# MOD-Z_01_V02.net
KiCad netlist of a schematic drawn in EAGLE
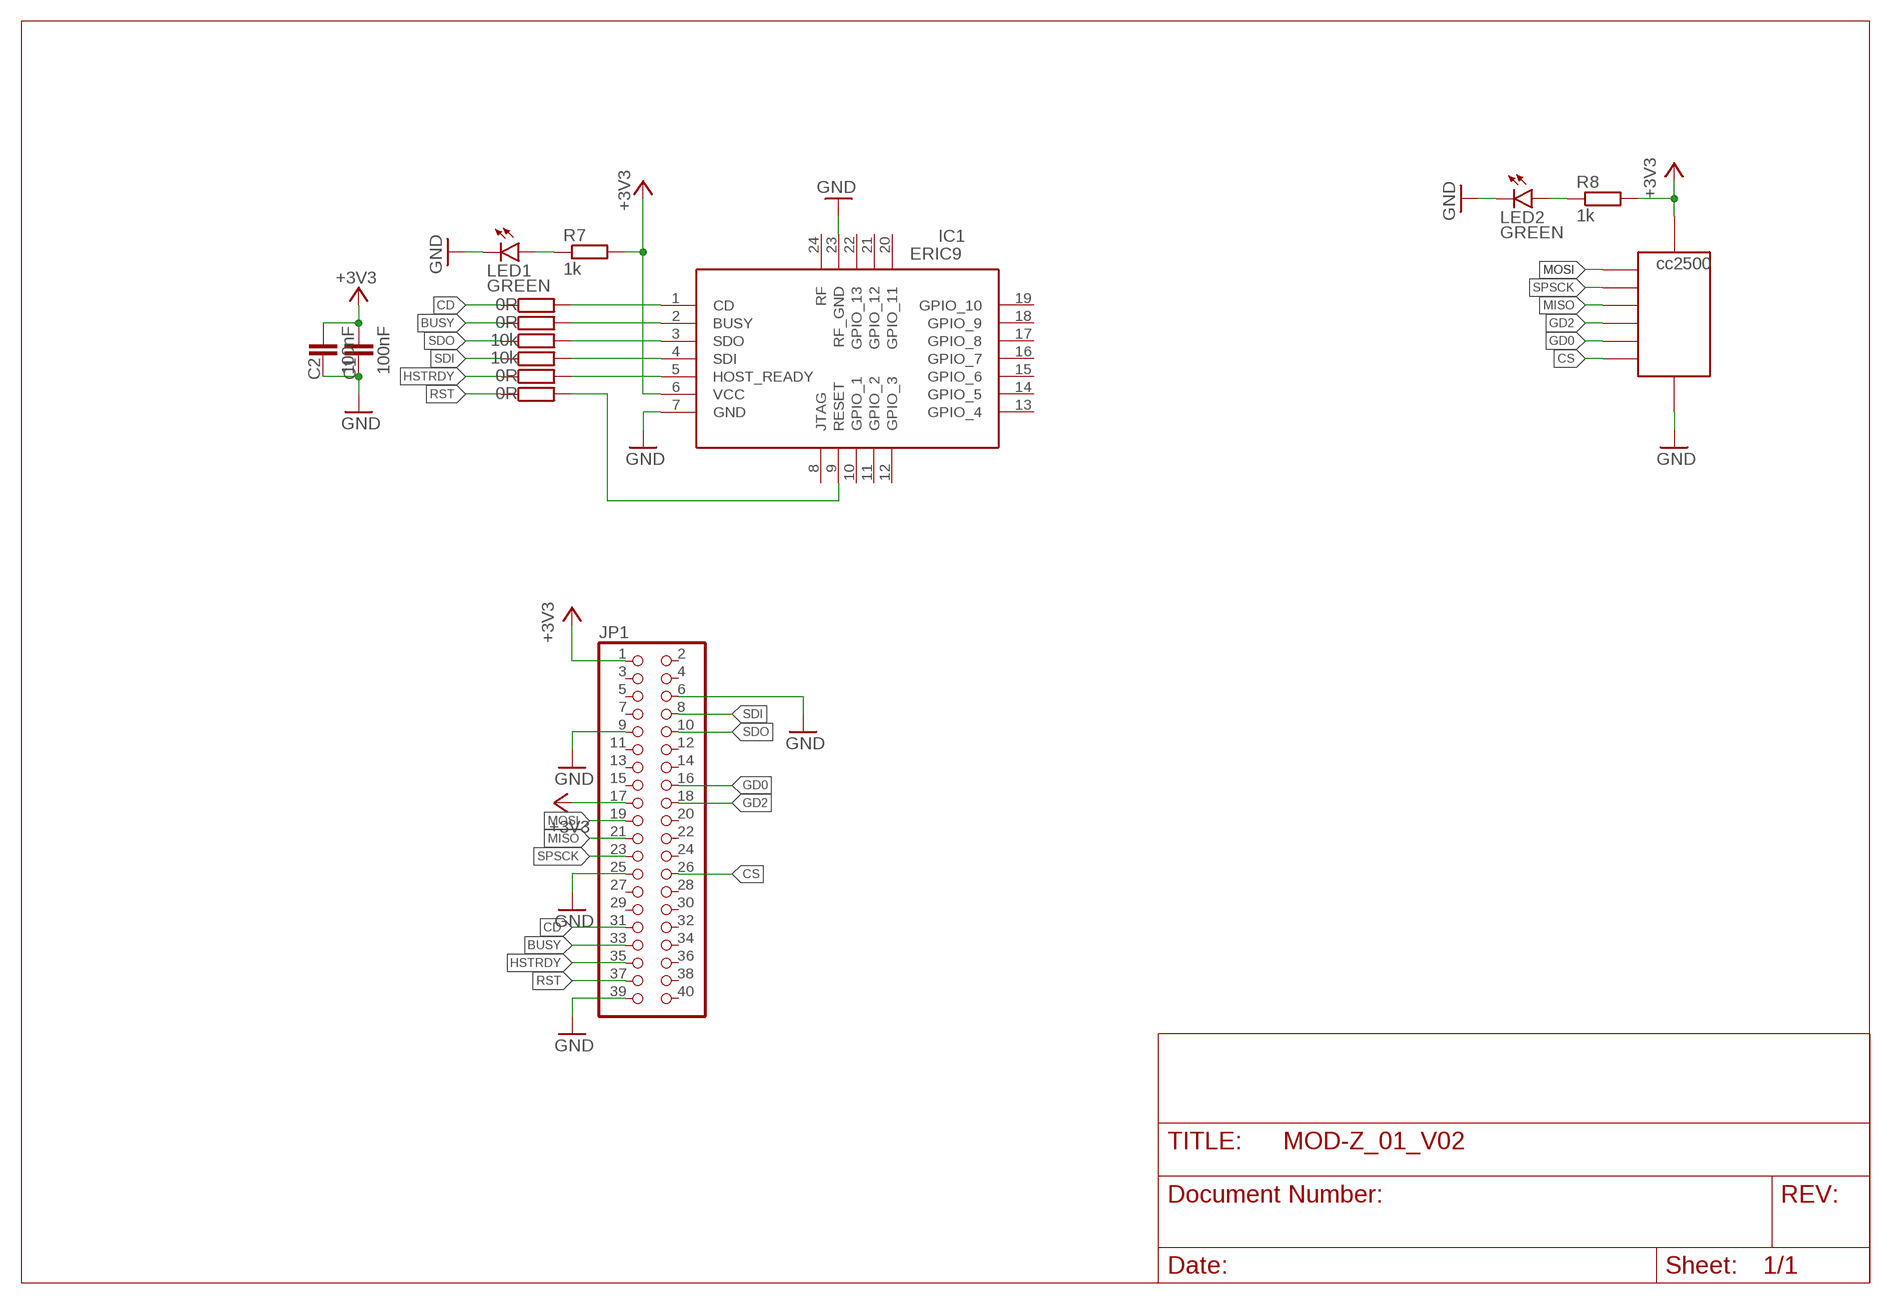
[diagram p0: schematic, sheet 1]

(export (version "E")
  (design (tool "Eeschema 10.0.6"))
  (components
    (comp (ref "C1")
      (value "100nF")
      (footprint "eagle-import:C0805")
      (libsource (lib "eagle-import") (part "C-EUC0805"))
    )
    (comp (ref "C2")
      (value "100nF")
      (footprint "eagle-import:C0805")
      (libsource (lib "eagle-import") (part "C-EUC0805"))
    )
    (comp (ref "IC1")
      (value "ERIC9")
      (footprint "eagle-import:ERIC9")
      (fields (field (name "MANUFACTURER_PART_NUMBER") "eRIC9"))
      (libsource (lib "eagle-import") (part "ERIC9"))
    )
    (comp (ref "IC2")
      (value "CC2500")
      (footprint "eagle-import:CC2500")
      (libsource (lib "eagle-import") (part "CC2500"))
    )
    (comp (ref "JP1")
      (value "PINHD-2X20")
      (footprint "eagle-import:2X20")
      (libsource (lib "eagle-import") (part "PINHD-2X20"))
    )
    (comp (ref "LED1")
      (value "GREEN")
      (footprint "eagle-import:CHIP-LED0805")
      (libsource (lib "eagle-import") (part "LEDCHIP-LED0805"))
    )
    (comp (ref "LED2")
      (value "GREEN")
      (footprint "eagle-import:CHIP-LED0805")
      (libsource (lib "eagle-import") (part "LEDCHIP-LED0805"))
    )
    (comp (ref "R1")
      (value "0R")
      (footprint "eagle-import:R0805")
      (libsource (lib "eagle-import") (part "R-EU_R0805"))
    )
    (comp (ref "R2")
      (value "0R")
      (footprint "eagle-import:R0805")
      (libsource (lib "eagle-import") (part "R-EU_R0805"))
    )
    (comp (ref "R3")
      (value "10k")
      (footprint "eagle-import:R0805")
      (libsource (lib "eagle-import") (part "R-EU_R0805"))
    )
    (comp (ref "R4")
      (value "10k")
      (footprint "eagle-import:R0805")
      (libsource (lib "eagle-import") (part "R-EU_R0805"))
    )
    (comp (ref "R5")
      (value "0R")
      (footprint "eagle-import:R0805")
      (libsource (lib "eagle-import") (part "R-EU_R0805"))
    )
    (comp (ref "R6")
      (value "0R")
      (footprint "eagle-import:R0805")
      (libsource (lib "eagle-import") (part "R-EU_R0805"))
    )
    (comp (ref "R7")
      (value "1k")
      (footprint "eagle-import:R0805")
      (libsource (lib "eagle-import") (part "R-EU_R0805"))
    )
    (comp (ref "R8")
      (value "1k")
      (footprint "eagle-import:R0805")
      (libsource (lib "eagle-import") (part "R-EU_R0805"))
    )
  )
  (nets
    (net (code "1") (name "+3V3") (class "Default")
      (node (ref "C1") (pin "1") (pinfunction "1_1") (pintype "passive"))
      (node (ref "C2") (pin "1") (pinfunction "1_1") (pintype "passive"))
      (node (ref "IC1") (pin "6") (pinfunction "VCC_6") (pintype "bidirectional"))
      (node (ref "IC2") (pin "+3V3") (pinfunction "+3V3_+3V3") (pintype "power_in"))
      (node (ref "JP1") (pin "1") (pinfunction "1_1") (pintype "passive"))
      (node (ref "JP1") (pin "17") (pinfunction "17_17") (pintype "passive"))
      (node (ref "R7") (pin "2") (pinfunction "2_2") (pintype "passive"))
      (node (ref "R8") (pin "2") (pinfunction "2_2") (pintype "passive"))
    )
    (net (code "2") (name "BUSY") (class "Default")
      (node (ref "JP1") (pin "33") (pinfunction "33_33") (pintype "passive"))
      (node (ref "R2") (pin "1") (pinfunction "1_1") (pintype "passive"))
    )
    (net (code "3") (name "CD") (class "Default")
      (node (ref "JP1") (pin "31") (pinfunction "31_31") (pintype "passive"))
      (node (ref "R1") (pin "1") (pinfunction "1_1") (pintype "passive"))
    )
    (net (code "4") (name "CS") (class "Default")
      (node (ref "IC2") (pin "CS") (pinfunction "CS_CS") (pintype "bidirectional"))
      (node (ref "JP1") (pin "26") (pinfunction "26_26") (pintype "passive"))
    )
    (net (code "5") (name "GD0") (class "Default")
      (node (ref "IC2") (pin "SPSCK") (pinfunction "SPSCK_SPSCK") (pintype "bidirectional"))
      (node (ref "JP1") (pin "16") (pinfunction "16_16") (pintype "passive"))
    )
    (net (code "6") (name "GD2") (class "Default")
      (node (ref "IC2") (pin "MOSI") (pinfunction "MOSI_MOSI") (pintype "bidirectional"))
      (node (ref "JP1") (pin "18") (pinfunction "18_18") (pintype "passive"))
    )
    (net (code "7") (name "GND") (class "Default")
      (node (ref "C1") (pin "2") (pinfunction "2_2") (pintype "passive"))
      (node (ref "C2") (pin "2") (pinfunction "2_2") (pintype "passive"))
      (node (ref "IC1") (pin "23") (pinfunction "RF_GND_23") (pintype "bidirectional"))
      (node (ref "IC1") (pin "7") (pinfunction "GND_7") (pintype "bidirectional"))
      (node (ref "IC2") (pin "GND") (pinfunction "GND_GND") (pintype "power_in"))
      (node (ref "JP1") (pin "25") (pinfunction "25_25") (pintype "passive"))
      (node (ref "JP1") (pin "39") (pinfunction "39_39") (pintype "passive"))
      (node (ref "JP1") (pin "6") (pinfunction "6_6") (pintype "passive"))
      (node (ref "JP1") (pin "9") (pinfunction "9_9") (pintype "passive"))
      (node (ref "LED1") (pin "C") (pinfunction "C_C") (pintype "passive"))
      (node (ref "LED2") (pin "C") (pinfunction "C_C") (pintype "passive"))
    )
    (net (code "8") (name "HSTRDY") (class "Default")
      (node (ref "JP1") (pin "35") (pinfunction "35_35") (pintype "passive"))
      (node (ref "R5") (pin "1") (pinfunction "1_1") (pintype "passive"))
    )
    (net (code "9") (name "MISO") (class "Default")
      (node (ref "IC2") (pin "MISO") (pinfunction "MISO_MISO") (pintype "bidirectional"))
      (node (ref "JP1") (pin "21") (pinfunction "21_21") (pintype "passive"))
    )
    (net (code "10") (name "MOSI") (class "Default")
      (node (ref "IC2") (pin "GD0") (pinfunction "GD0_GD0") (pintype "bidirectional"))
      (node (ref "JP1") (pin "19") (pinfunction "19_19") (pintype "passive"))
    )
    (net (code "11") (name "Net-(IC1-BUSY)") (class "Default")
      (node (ref "IC1") (pin "2") (pinfunction "BUSY_2") (pintype "bidirectional"))
      (node (ref "R2") (pin "2") (pinfunction "2_2") (pintype "passive"))
    )
    (net (code "12") (name "Net-(IC1-CD)") (class "Default")
      (node (ref "IC1") (pin "1") (pinfunction "CD_1") (pintype "bidirectional"))
      (node (ref "R1") (pin "2") (pinfunction "2_2") (pintype "passive"))
    )
    (net (code "13") (name "Net-(IC1-HOST_READY)") (class "Default")
      (node (ref "IC1") (pin "5") (pinfunction "HOST_READY_5") (pintype "bidirectional"))
      (node (ref "R5") (pin "2") (pinfunction "2_2") (pintype "passive"))
    )
    (net (code "14") (name "Net-(IC1-RESET)") (class "Default")
      (node (ref "IC1") (pin "9") (pinfunction "RESET_9") (pintype "bidirectional"))
      (node (ref "R6") (pin "2") (pinfunction "2_2") (pintype "passive"))
    )
    (net (code "15") (name "Net-(IC1-SDI)") (class "Default")
      (node (ref "IC1") (pin "4") (pinfunction "SDI_4") (pintype "bidirectional"))
      (node (ref "R4") (pin "2") (pinfunction "2_2") (pintype "passive"))
    )
    (net (code "16") (name "Net-(IC1-SDO)") (class "Default")
      (node (ref "IC1") (pin "3") (pinfunction "SDO_3") (pintype "bidirectional"))
      (node (ref "R3") (pin "2") (pinfunction "2_2") (pintype "passive"))
    )
    (net (code "17") (name "Net-(LED1-PadA)") (class "Default")
      (node (ref "LED1") (pin "A") (pinfunction "A_A") (pintype "passive"))
      (node (ref "R7") (pin "1") (pinfunction "1_1") (pintype "passive"))
    )
    (net (code "18") (name "Net-(LED2-PadA)") (class "Default")
      (node (ref "LED2") (pin "A") (pinfunction "A_A") (pintype "passive"))
      (node (ref "R8") (pin "1") (pinfunction "1_1") (pintype "passive"))
    )
    (net (code "19") (name "RST") (class "Default")
      (node (ref "JP1") (pin "37") (pinfunction "37_37") (pintype "passive"))
      (node (ref "R6") (pin "1") (pinfunction "1_1") (pintype "passive"))
    )
    (net (code "20") (name "SDI") (class "Default")
      (node (ref "JP1") (pin "8") (pinfunction "8_8") (pintype "passive"))
      (node (ref "R4") (pin "1") (pinfunction "1_1") (pintype "passive"))
    )
    (net (code "21") (name "SDO") (class "Default")
      (node (ref "JP1") (pin "10") (pinfunction "10_10") (pintype "passive"))
      (node (ref "R3") (pin "1") (pinfunction "1_1") (pintype "passive"))
    )
    (net (code "22") (name "SPSCK") (class "Default")
      (node (ref "IC2") (pin "GD2") (pinfunction "GD2_GD2") (pintype "bidirectional"))
      (node (ref "JP1") (pin "23") (pinfunction "23_23") (pintype "passive"))
    )
    (net (code "23") (name "unconnected-(IC1-GPIO_1-Pad10)") (class "Default")
      (node (ref "IC1") (pin "10") (pinfunction "GPIO_1_10") (pintype "bidirectional"))
    )
    (net (code "24") (name "unconnected-(IC1-GPIO_2-Pad11)") (class "Default")
      (node (ref "IC1") (pin "11") (pinfunction "GPIO_2_11") (pintype "bidirectional"))
    )
    (net (code "25") (name "unconnected-(IC1-GPIO_3-Pad12)") (class "Default")
      (node (ref "IC1") (pin "12") (pinfunction "GPIO_3_12") (pintype "bidirectional"))
    )
    (net (code "26") (name "unconnected-(IC1-GPIO_4-Pad13)") (class "Default")
      (node (ref "IC1") (pin "13") (pinfunction "GPIO_4_13") (pintype "bidirectional"))
    )
    (net (code "27") (name "unconnected-(IC1-GPIO_5-Pad14)") (class "Default")
      (node (ref "IC1") (pin "14") (pinfunction "GPIO_5_14") (pintype "bidirectional"))
    )
    (net (code "28") (name "unconnected-(IC1-GPIO_6-Pad15)") (class "Default")
      (node (ref "IC1") (pin "15") (pinfunction "GPIO_6_15") (pintype "bidirectional"))
    )
    (net (code "29") (name "unconnected-(IC1-GPIO_7-Pad16)") (class "Default")
      (node (ref "IC1") (pin "16") (pinfunction "GPIO_7_16") (pintype "bidirectional"))
    )
    (net (code "30") (name "unconnected-(IC1-GPIO_8-Pad17)") (class "Default")
      (node (ref "IC1") (pin "17") (pinfunction "GPIO_8_17") (pintype "bidirectional"))
    )
    (net (code "31") (name "unconnected-(IC1-GPIO_9-Pad18)") (class "Default")
      (node (ref "IC1") (pin "18") (pinfunction "GPIO_9_18") (pintype "bidirectional"))
    )
    (net (code "32") (name "unconnected-(IC1-GPIO_10-Pad19)") (class "Default")
      (node (ref "IC1") (pin "19") (pinfunction "GPIO_10_19") (pintype "bidirectional"))
    )
    (net (code "33") (name "unconnected-(IC1-GPIO_11-Pad20)") (class "Default")
      (node (ref "IC1") (pin "20") (pinfunction "GPIO_11_20") (pintype "bidirectional"))
    )
    (net (code "34") (name "unconnected-(IC1-GPIO_12-Pad21)") (class "Default")
      (node (ref "IC1") (pin "21") (pinfunction "GPIO_12_21") (pintype "bidirectional"))
    )
    (net (code "35") (name "unconnected-(IC1-GPIO_13-Pad22)") (class "Default")
      (node (ref "IC1") (pin "22") (pinfunction "GPIO_13_22") (pintype "bidirectional"))
    )
    (net (code "36") (name "unconnected-(IC1-JTAG-Pad8)") (class "Default")
      (node (ref "IC1") (pin "8") (pinfunction "JTAG_8") (pintype "bidirectional"))
    )
    (net (code "37") (name "unconnected-(IC1-RF-Pad24)") (class "Default")
      (node (ref "IC1") (pin "24") (pinfunction "RF_24") (pintype "bidirectional"))
    )
    (net (code "38") (name "unconnected-(JP1-Pad2)") (class "Default")
      (node (ref "JP1") (pin "2") (pinfunction "2_2") (pintype "passive"))
    )
    (net (code "39") (name "unconnected-(JP1-Pad3)") (class "Default")
      (node (ref "JP1") (pin "3") (pinfunction "3_3") (pintype "passive"))
    )
    (net (code "40") (name "unconnected-(JP1-Pad4)") (class "Default")
      (node (ref "JP1") (pin "4") (pinfunction "4_4") (pintype "passive"))
    )
    (net (code "41") (name "unconnected-(JP1-Pad5)") (class "Default")
      (node (ref "JP1") (pin "5") (pinfunction "5_5") (pintype "passive"))
    )
    (net (code "42") (name "unconnected-(JP1-Pad7)") (class "Default")
      (node (ref "JP1") (pin "7") (pinfunction "7_7") (pintype "passive"))
    )
    (net (code "43") (name "unconnected-(JP1-Pad11)") (class "Default")
      (node (ref "JP1") (pin "11") (pinfunction "11_11") (pintype "passive"))
    )
    (net (code "44") (name "unconnected-(JP1-Pad12)") (class "Default")
      (node (ref "JP1") (pin "12") (pinfunction "12_12") (pintype "passive"))
    )
    (net (code "45") (name "unconnected-(JP1-Pad13)") (class "Default")
      (node (ref "JP1") (pin "13") (pinfunction "13_13") (pintype "passive"))
    )
    (net (code "46") (name "unconnected-(JP1-Pad14)") (class "Default")
      (node (ref "JP1") (pin "14") (pinfunction "14_14") (pintype "passive"))
    )
    (net (code "47") (name "unconnected-(JP1-Pad15)") (class "Default")
      (node (ref "JP1") (pin "15") (pinfunction "15_15") (pintype "passive"))
    )
    (net (code "48") (name "unconnected-(JP1-Pad20)") (class "Default")
      (node (ref "JP1") (pin "20") (pinfunction "20_20") (pintype "passive"))
    )
    (net (code "49") (name "unconnected-(JP1-Pad22)") (class "Default")
      (node (ref "JP1") (pin "22") (pinfunction "22_22") (pintype "passive"))
    )
    (net (code "50") (name "unconnected-(JP1-Pad24)") (class "Default")
      (node (ref "JP1") (pin "24") (pinfunction "24_24") (pintype "passive"))
    )
    (net (code "51") (name "unconnected-(JP1-Pad27)") (class "Default")
      (node (ref "JP1") (pin "27") (pinfunction "27_27") (pintype "passive"))
    )
    (net (code "52") (name "unconnected-(JP1-Pad28)") (class "Default")
      (node (ref "JP1") (pin "28") (pinfunction "28_28") (pintype "passive"))
    )
    (net (code "53") (name "unconnected-(JP1-Pad29)") (class "Default")
      (node (ref "JP1") (pin "29") (pinfunction "29_29") (pintype "passive"))
    )
    (net (code "54") (name "unconnected-(JP1-Pad30)") (class "Default")
      (node (ref "JP1") (pin "30") (pinfunction "30_30") (pintype "passive"))
    )
    (net (code "55") (name "unconnected-(JP1-Pad32)") (class "Default")
      (node (ref "JP1") (pin "32") (pinfunction "32_32") (pintype "passive"))
    )
    (net (code "56") (name "unconnected-(JP1-Pad34)") (class "Default")
      (node (ref "JP1") (pin "34") (pinfunction "34_34") (pintype "passive"))
    )
    (net (code "57") (name "unconnected-(JP1-Pad36)") (class "Default")
      (node (ref "JP1") (pin "36") (pinfunction "36_36") (pintype "passive"))
    )
    (net (code "58") (name "unconnected-(JP1-Pad38)") (class "Default")
      (node (ref "JP1") (pin "38") (pinfunction "38_38") (pintype "passive"))
    )
    (net (code "59") (name "unconnected-(JP1-Pad40)") (class "Default")
      (node (ref "JP1") (pin "40") (pinfunction "40_40") (pintype "passive"))
    )
  )
)
